# KSS_4_button.net
KiCad netlist of a schematic drawn in Altium Designer
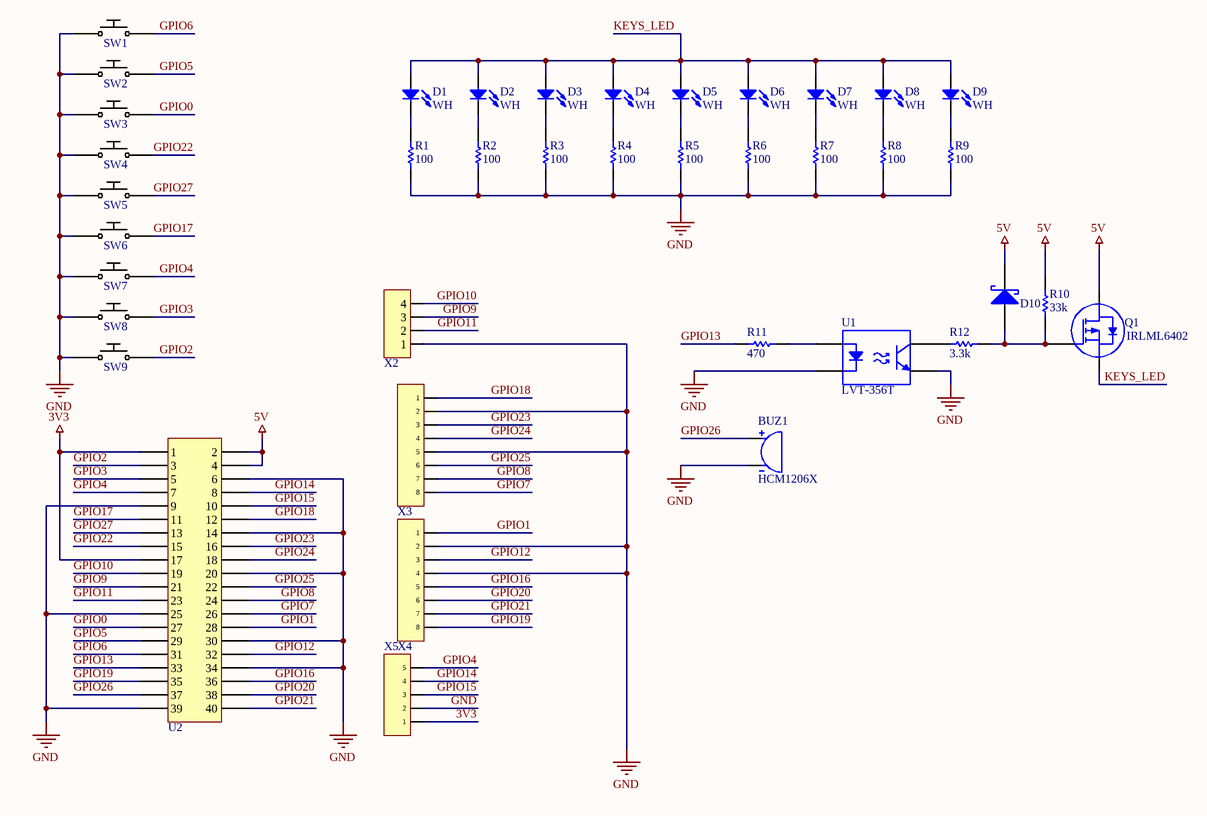
[diagram p0: KSS_4_button.SchDoc]

(export (version "E")
  (design (tool "Eeschema 10.0.6"))
  (components
    (comp (ref "BUZ1")
      (value "HCM1206X")
      (footprint "HCM1206X")
      (description "Buzzer")
      (libsource (lib "COMPONENTS_2022") (part "HCM1206X"))
    )
    (comp (ref "D1")
      (value "WH")
      (footprint "LED_1206/3mm")
      (libsource (lib "COMPONENTS_2022") (part "Diode LED"))
    )
    (comp (ref "D2")
      (value "WH")
      (footprint "LED_1206/3mm")
      (libsource (lib "COMPONENTS_2022") (part "Diode LED"))
    )
    (comp (ref "D3")
      (value "WH")
      (footprint "LED_1206/3mm")
      (libsource (lib "COMPONENTS_2022") (part "Diode LED"))
    )
    (comp (ref "D4")
      (value "WH")
      (footprint "LED_1206/3mm")
      (libsource (lib "COMPONENTS_2022") (part "Diode LED"))
    )
    (comp (ref "D5")
      (value "WH")
      (footprint "LED_1206/3mm")
      (libsource (lib "COMPONENTS_2022") (part "Diode LED"))
    )
    (comp (ref "D6")
      (value "WH")
      (footprint "LED_1206/3mm")
      (libsource (lib "COMPONENTS_2022") (part "Diode LED"))
    )
    (comp (ref "D7")
      (value "WH")
      (footprint "LED_1206/3mm")
      (libsource (lib "COMPONENTS_2022") (part "Diode LED"))
    )
    (comp (ref "D8")
      (value "WH")
      (footprint "LED_1206/3mm")
      (libsource (lib "COMPONENTS_2022") (part "Diode LED"))
    )
    (comp (ref "D9")
      (value "WH")
      (footprint "LED_1206/3mm")
      (libsource (lib "COMPONENTS_2022") (part "Diode LED"))
    )
    (comp (ref "D10")
      (value "SS14")
      (footprint "SMA/DO-214AC")
      (description "Schottky")
      (libsource (lib "COMPONENTS_2022") (part "SS14"))
    )
    (comp (ref "Q1")
      (value "IRLML6402")
      (footprint "SOT23_3_PIN")
      (description "P-MOSFET")
      (libsource (lib "COMPONENTS_2022") (part "IRLML6402"))
    )
    (comp (ref "R1")
      (value "Resistor")
      (fields (field (name "RESISTANCE") "100"))
      (libsource (lib "COMPONENTS_2022") (part "Resistor"))
    )
    (comp (ref "R2")
      (value "Resistor")
      (fields (field (name "RESISTANCE") "100"))
      (libsource (lib "COMPONENTS_2022") (part "Resistor"))
    )
    (comp (ref "R3")
      (value "Resistor")
      (fields (field (name "RESISTANCE") "100"))
      (libsource (lib "COMPONENTS_2022") (part "Resistor"))
    )
    (comp (ref "R4")
      (value "Resistor")
      (fields (field (name "RESISTANCE") "100"))
      (libsource (lib "COMPONENTS_2022") (part "Resistor"))
    )
    (comp (ref "R5")
      (value "Resistor")
      (fields (field (name "RESISTANCE") "100"))
      (libsource (lib "COMPONENTS_2022") (part "Resistor"))
    )
    (comp (ref "R6")
      (value "Resistor")
      (fields (field (name "RESISTANCE") "100"))
      (libsource (lib "COMPONENTS_2022") (part "Resistor"))
    )
    (comp (ref "R7")
      (value "Resistor")
      (fields (field (name "RESISTANCE") "100"))
      (libsource (lib "COMPONENTS_2022") (part "Resistor"))
    )
    (comp (ref "R8")
      (value "Resistor")
      (fields (field (name "RESISTANCE") "100"))
      (libsource (lib "COMPONENTS_2022") (part "Resistor"))
    )
    (comp (ref "R9")
      (value "Resistor")
      (fields (field (name "RESISTANCE") "100"))
      (libsource (lib "COMPONENTS_2022") (part "Resistor"))
    )
    (comp (ref "R10")
      (value "Resistor")
      (footprint "RES_0603")
      (fields (field (name "RESISTANCE") "33k"))
      (libsource (lib "COMPONENTS_2022") (part "Resistor"))
    )
    (comp (ref "R11")
      (value "Resistor")
      (footprint "RES_0603")
      (fields (field (name "RESISTANCE") "470"))
      (libsource (lib "COMPONENTS_2022") (part "Resistor"))
    )
    (comp (ref "R12")
      (value "Resistor")
      (footprint "RES_0603")
      (fields (field (name "RESISTANCE") "3.3k"))
      (libsource (lib "COMPONENTS_2022") (part "Resistor"))
    )
    (comp (ref "SW1")
      (value "Pushbutton")
      (footprint "Key switch Outemu")
      (libsource (lib "COMPONENTS_2022") (part "Pushbutton"))
    )
    (comp (ref "SW2")
      (value "Pushbutton")
      (footprint "Key switch Outemu")
      (libsource (lib "COMPONENTS_2022") (part "Pushbutton"))
    )
    (comp (ref "SW3")
      (value "Pushbutton")
      (footprint "Key switch Outemu")
      (libsource (lib "COMPONENTS_2022") (part "Pushbutton"))
    )
    (comp (ref "SW4")
      (value "Pushbutton")
      (footprint "Key switch Outemu")
      (libsource (lib "COMPONENTS_2022") (part "Pushbutton"))
    )
    (comp (ref "SW5")
      (value "Pushbutton")
      (footprint "Key switch Outemu")
      (libsource (lib "COMPONENTS_2022") (part "Pushbutton"))
    )
    (comp (ref "SW6")
      (value "Pushbutton")
      (footprint "Key switch Outemu")
      (libsource (lib "COMPONENTS_2022") (part "Pushbutton"))
    )
    (comp (ref "SW7")
      (value "Pushbutton")
      (footprint "Key switch Outemu")
      (libsource (lib "COMPONENTS_2022") (part "Pushbutton"))
    )
    (comp (ref "SW8")
      (value "Pushbutton")
      (footprint "Key switch Outemu")
      (libsource (lib "COMPONENTS_2022") (part "Pushbutton"))
    )
    (comp (ref "SW9")
      (value "Pushbutton")
      (footprint "Key switch Outemu")
      (libsource (lib "COMPONENTS_2022") (part "Pushbutton"))
    )
    (comp (ref "U1")
      (value "LVT-356T")
      (footprint "SOP-4")
      (description "Optocoupler")
      (libsource (lib "COMPONENTS_2022") (part "LVT-356T"))
    )
    (comp (ref "U2")
      (value "RASPBERRY_PI_ZERO_W2")
      (footprint "RASPBERRY_PI_ZERO_W2")
      (libsource (lib "COMPONENTS_2022") (part "RASPBERRY_PI_ZERO_W2"))
    )
    (comp (ref "X2")
      (value "Connector_x4")
      (footprint "GROVE_4_pin_2mm_socket")
      (libsource (lib "COMPONENTS_2022") (part "Connector_x4"))
    )
    (comp (ref "X3")
      (value "HEADER_X8")
      (footprint "HEADER_1X8_F")
      (libsource (lib "HEADERS") (part "HEADER_X8"))
    )
    (comp (ref "X4")
      (value "HEADER_X8")
      (footprint "HEADER_1X8_F")
      (libsource (lib "HEADERS") (part "HEADER_X8"))
    )
    (comp (ref "X5") (value "GPS") (footprint "HEADER_1X5_F") (libsource (lib "HEADERS") (part "HEADER_X5")))
  )
  (nets
    (net (code "1") (name "/GPIO0") (class "Default")
      (node (ref "SW3") (pin "2") (pinfunction "2_2") (pintype "passive"))
      (node (ref "U2") (pin "27") (pinfunction "27_27") (pintype "passive"))
    )
    (net (code "2") (name "/GPIO1") (class "Default")
      (node (ref "U2") (pin "28") (pinfunction "28_28") (pintype "passive"))
      (node (ref "X4") (pin "1") (pinfunction "1_1") (pintype "passive"))
    )
    (net (code "3") (name "/GPIO2") (class "Default")
      (node (ref "SW9") (pin "2") (pinfunction "2_2") (pintype "passive"))
      (node (ref "U2") (pin "3") (pinfunction "3_3") (pintype "passive"))
    )
    (net (code "4") (name "/GPIO3") (class "Default")
      (node (ref "SW8") (pin "2") (pinfunction "2_2") (pintype "passive"))
      (node (ref "U2") (pin "5") (pinfunction "5_5") (pintype "passive"))
    )
    (net (code "5") (name "/GPIO4") (class "Default")
      (node (ref "SW7") (pin "2") (pinfunction "2_2") (pintype "passive"))
      (node (ref "U2") (pin "7") (pinfunction "7_7") (pintype "passive"))
      (node (ref "X5") (pin "5") (pinfunction "5_5") (pintype "passive"))
    )
    (net (code "6") (name "/GPIO5") (class "Default")
      (node (ref "SW2") (pin "2") (pinfunction "2_2") (pintype "passive"))
      (node (ref "U2") (pin "29") (pinfunction "29_29") (pintype "passive"))
    )
    (net (code "7") (name "/GPIO6") (class "Default")
      (node (ref "SW1") (pin "2") (pinfunction "2_2") (pintype "passive"))
      (node (ref "U2") (pin "31") (pinfunction "31_31") (pintype "passive"))
    )
    (net (code "8") (name "/GPIO7") (class "Default")
      (node (ref "U2") (pin "26") (pinfunction "26_26") (pintype "passive"))
      (node (ref "X3") (pin "8") (pinfunction "8_8") (pintype "passive"))
    )
    (net (code "9") (name "/GPIO8") (class "Default")
      (node (ref "U2") (pin "24") (pinfunction "24_24") (pintype "passive"))
      (node (ref "X3") (pin "7") (pinfunction "7_7") (pintype "passive"))
    )
    (net (code "10") (name "/GPIO9") (class "Default")
      (node (ref "U2") (pin "21") (pinfunction "21_21") (pintype "passive"))
      (node (ref "X2") (pin "3") (pinfunction "3_3") (pintype "passive"))
    )
    (net (code "11") (name "/GPIO10") (class "Default")
      (node (ref "U2") (pin "19") (pinfunction "19_19") (pintype "passive"))
      (node (ref "X2") (pin "4") (pinfunction "4_4") (pintype "passive"))
    )
    (net (code "12") (name "/GPIO11") (class "Default")
      (node (ref "U2") (pin "23") (pinfunction "23_23") (pintype "passive"))
      (node (ref "X2") (pin "2") (pinfunction "2_2") (pintype "passive"))
    )
    (net (code "13") (name "/GPIO12") (class "Default")
      (node (ref "U2") (pin "32") (pinfunction "32_32") (pintype "passive"))
      (node (ref "X4") (pin "3") (pinfunction "3_3") (pintype "passive"))
    )
    (net (code "14") (name "/GPIO13") (class "Default")
      (node (ref "R11") (pin "1") (pinfunction "1_1") (pintype "passive"))
      (node (ref "U2") (pin "33") (pinfunction "33_33") (pintype "passive"))
    )
    (net (code "15") (name "/GPIO14") (class "Default")
      (node (ref "U2") (pin "8") (pinfunction "8_8") (pintype "passive"))
      (node (ref "X5") (pin "4") (pinfunction "4_4") (pintype "passive"))
    )
    (net (code "16") (name "/GPIO15") (class "Default")
      (node (ref "U2") (pin "10") (pinfunction "10_10") (pintype "passive"))
      (node (ref "X5") (pin "3") (pinfunction "3_3") (pintype "passive"))
    )
    (net (code "17") (name "/GPIO16") (class "Default")
      (node (ref "U2") (pin "36") (pinfunction "36_36") (pintype "passive"))
      (node (ref "X4") (pin "5") (pinfunction "5_5") (pintype "passive"))
    )
    (net (code "18") (name "/GPIO17") (class "Default")
      (node (ref "SW6") (pin "2") (pinfunction "2_2") (pintype "passive"))
      (node (ref "U2") (pin "11") (pinfunction "11_11") (pintype "passive"))
    )
    (net (code "19") (name "/GPIO18") (class "Default")
      (node (ref "U2") (pin "12") (pinfunction "12_12") (pintype "passive"))
      (node (ref "X3") (pin "1") (pinfunction "1_1") (pintype "passive"))
    )
    (net (code "20") (name "/GPIO19") (class "Default")
      (node (ref "U2") (pin "35") (pinfunction "35_35") (pintype "passive"))
      (node (ref "X4") (pin "8") (pinfunction "8_8") (pintype "passive"))
    )
    (net (code "21") (name "/GPIO20") (class "Default")
      (node (ref "U2") (pin "38") (pinfunction "38_38") (pintype "passive"))
      (node (ref "X4") (pin "6") (pinfunction "6_6") (pintype "passive"))
    )
    (net (code "22") (name "/GPIO21") (class "Default")
      (node (ref "U2") (pin "40") (pinfunction "40_40") (pintype "passive"))
      (node (ref "X4") (pin "7") (pinfunction "7_7") (pintype "passive"))
    )
    (net (code "23") (name "/GPIO22") (class "Default")
      (node (ref "SW4") (pin "2") (pinfunction "2_2") (pintype "passive"))
      (node (ref "U2") (pin "15") (pinfunction "15_15") (pintype "passive"))
    )
    (net (code "24") (name "/GPIO23") (class "Default")
      (node (ref "U2") (pin "16") (pinfunction "16_16") (pintype "passive"))
      (node (ref "X3") (pin "3") (pinfunction "3_3") (pintype "passive"))
    )
    (net (code "25") (name "/GPIO24") (class "Default")
      (node (ref "U2") (pin "18") (pinfunction "18_18") (pintype "passive"))
      (node (ref "X3") (pin "4") (pinfunction "4_4") (pintype "passive"))
    )
    (net (code "26") (name "/GPIO25") (class "Default")
      (node (ref "U2") (pin "22") (pinfunction "22_22") (pintype "passive"))
      (node (ref "X3") (pin "6") (pinfunction "6_6") (pintype "passive"))
    )
    (net (code "27") (name "/GPIO26") (class "Default")
      (node (ref "BUZ1") (pin "1") (pinfunction "+_1") (pintype "passive"))
      (node (ref "U2") (pin "37") (pinfunction "37_37") (pintype "passive"))
    )
    (net (code "28") (name "/GPIO27") (class "Default")
      (node (ref "SW5") (pin "2") (pinfunction "2_2") (pintype "passive"))
      (node (ref "U2") (pin "13") (pinfunction "13_13") (pintype "passive"))
    )
    (net (code "29") (name "/KEYS_LED") (class "Default")
      (node (ref "D1") (pin "1") (pinfunction "A_1") (pintype "passive"))
      (node (ref "D2") (pin "1") (pinfunction "A_1") (pintype "passive"))
      (node (ref "D3") (pin "1") (pinfunction "A_1") (pintype "passive"))
      (node (ref "D4") (pin "1") (pinfunction "A_1") (pintype "passive"))
      (node (ref "D5") (pin "1") (pinfunction "A_1") (pintype "passive"))
      (node (ref "D6") (pin "1") (pinfunction "A_1") (pintype "passive"))
      (node (ref "D7") (pin "1") (pinfunction "A_1") (pintype "passive"))
      (node (ref "D8") (pin "1") (pinfunction "A_1") (pintype "passive"))
      (node (ref "D9") (pin "1") (pinfunction "A_1") (pintype "passive"))
      (node (ref "Q1") (pin "2") (pinfunction "S_2") (pintype "passive"))
    )
    (net (code "30") (name "3V3") (class "Default")
      (node (ref "U2") (pin "1") (pinfunction "1_1") (pintype "passive"))
      (node (ref "U2") (pin "17") (pinfunction "17_17") (pintype "passive"))
      (node (ref "X5") (pin "1") (pinfunction "1_1") (pintype "passive"))
    )
    (net (code "31") (name "5V") (class "Default")
      (node (ref "D10") (pin "2") (pinfunction "K_2") (pintype "passive"))
      (node (ref "Q1") (pin "3") (pinfunction "D_3") (pintype "passive"))
      (node (ref "R10") (pin "1") (pinfunction "1_1") (pintype "passive"))
      (node (ref "U2") (pin "2") (pinfunction "2_2") (pintype "passive"))
      (node (ref "U2") (pin "4") (pinfunction "4_4") (pintype "passive"))
    )
    (net (code "32") (name "GND") (class "Default")
      (node (ref "BUZ1") (pin "2") (pinfunction "-_2") (pintype "passive"))
      (node (ref "R1") (pin "1") (pinfunction "1_1") (pintype "passive"))
      (node (ref "R2") (pin "1") (pinfunction "1_1") (pintype "passive"))
      (node (ref "R3") (pin "1") (pinfunction "1_1") (pintype "passive"))
      (node (ref "R4") (pin "1") (pinfunction "1_1") (pintype "passive"))
      (node (ref "R5") (pin "1") (pinfunction "1_1") (pintype "passive"))
      (node (ref "R6") (pin "1") (pinfunction "1_1") (pintype "passive"))
      (node (ref "R7") (pin "1") (pinfunction "1_1") (pintype "passive"))
      (node (ref "R8") (pin "1") (pinfunction "1_1") (pintype "passive"))
      (node (ref "R9") (pin "1") (pinfunction "1_1") (pintype "passive"))
      (node (ref "SW1") (pin "1") (pinfunction "1_1") (pintype "passive"))
      (node (ref "SW2") (pin "1") (pinfunction "1_1") (pintype "passive"))
      (node (ref "SW3") (pin "1") (pinfunction "1_1") (pintype "passive"))
      (node (ref "SW4") (pin "1") (pinfunction "1_1") (pintype "passive"))
      (node (ref "SW5") (pin "1") (pinfunction "1_1") (pintype "passive"))
      (node (ref "SW6") (pin "1") (pinfunction "1_1") (pintype "passive"))
      (node (ref "SW7") (pin "1") (pinfunction "1_1") (pintype "passive"))
      (node (ref "SW8") (pin "1") (pinfunction "1_1") (pintype "passive"))
      (node (ref "SW9") (pin "1") (pinfunction "1_1") (pintype "passive"))
      (node (ref "U1") (pin "2") (pinfunction "K_2") (pintype "passive"))
      (node (ref "U1") (pin "3") (pinfunction "E_3") (pintype "passive"))
      (node (ref "U2") (pin "14") (pinfunction "14_14") (pintype "passive"))
      (node (ref "U2") (pin "20") (pinfunction "20_20") (pintype "passive"))
      (node (ref "U2") (pin "25") (pinfunction "25_25") (pintype "passive"))
      (node (ref "U2") (pin "30") (pinfunction "30_30") (pintype "passive"))
      (node (ref "U2") (pin "34") (pinfunction "34_34") (pintype "passive"))
      (node (ref "U2") (pin "39") (pinfunction "39_39") (pintype "passive"))
      (node (ref "U2") (pin "6") (pinfunction "6_6") (pintype "passive"))
      (node (ref "U2") (pin "9") (pinfunction "9_9") (pintype "passive"))
      (node (ref "X2") (pin "1") (pinfunction "1_1") (pintype "passive"))
      (node (ref "X3") (pin "2") (pinfunction "2_2") (pintype "passive"))
      (node (ref "X3") (pin "5") (pinfunction "5_5") (pintype "passive"))
      (node (ref "X4") (pin "2") (pinfunction "2_2") (pintype "passive"))
      (node (ref "X4") (pin "4") (pinfunction "4_4") (pintype "passive"))
      (node (ref "X5") (pin "2") (pinfunction "2_2") (pintype "passive"))
    )
    (net (code "33") (name "Net-(D1-K)") (class "Default")
      (node (ref "D1") (pin "2") (pinfunction "K_2") (pintype "passive"))
      (node (ref "R1") (pin "2") (pinfunction "2_2") (pintype "passive"))
    )
    (net (code "34") (name "Net-(D2-K)") (class "Default")
      (node (ref "D2") (pin "2") (pinfunction "K_2") (pintype "passive"))
      (node (ref "R2") (pin "2") (pinfunction "2_2") (pintype "passive"))
    )
    (net (code "35") (name "Net-(D3-K)") (class "Default")
      (node (ref "D3") (pin "2") (pinfunction "K_2") (pintype "passive"))
      (node (ref "R3") (pin "2") (pinfunction "2_2") (pintype "passive"))
    )
    (net (code "36") (name "Net-(D4-K)") (class "Default")
      (node (ref "D4") (pin "2") (pinfunction "K_2") (pintype "passive"))
      (node (ref "R4") (pin "2") (pinfunction "2_2") (pintype "passive"))
    )
    (net (code "37") (name "Net-(D5-K)") (class "Default")
      (node (ref "D5") (pin "2") (pinfunction "K_2") (pintype "passive"))
      (node (ref "R5") (pin "2") (pinfunction "2_2") (pintype "passive"))
    )
    (net (code "38") (name "Net-(D6-K)") (class "Default")
      (node (ref "D6") (pin "2") (pinfunction "K_2") (pintype "passive"))
      (node (ref "R6") (pin "2") (pinfunction "2_2") (pintype "passive"))
    )
    (net (code "39") (name "Net-(D7-K)") (class "Default")
      (node (ref "D7") (pin "2") (pinfunction "K_2") (pintype "passive"))
      (node (ref "R7") (pin "2") (pinfunction "2_2") (pintype "passive"))
    )
    (net (code "40") (name "Net-(D8-K)") (class "Default")
      (node (ref "D8") (pin "2") (pinfunction "K_2") (pintype "passive"))
      (node (ref "R8") (pin "2") (pinfunction "2_2") (pintype "passive"))
    )
    (net (code "41") (name "Net-(D9-K)") (class "Default")
      (node (ref "D9") (pin "2") (pinfunction "K_2") (pintype "passive"))
      (node (ref "R9") (pin "2") (pinfunction "2_2") (pintype "passive"))
    )
    (net (code "42") (name "Net-(D10-A)") (class "Default")
      (node (ref "D10") (pin "1") (pinfunction "A_1") (pintype "passive"))
      (node (ref "Q1") (pin "1") (pinfunction "G_1") (pintype "passive"))
      (node (ref "R10") (pin "2") (pinfunction "2_2") (pintype "passive"))
      (node (ref "R12") (pin "2") (pinfunction "2_2") (pintype "passive"))
    )
    (net (code "43") (name "Net-(U1-A)") (class "Default")
      (node (ref "R11") (pin "2") (pinfunction "2_2") (pintype "passive"))
      (node (ref "U1") (pin "1") (pinfunction "A_1") (pintype "passive"))
    )
    (net (code "44") (name "Net-(U1-C)") (class "Default")
      (node (ref "R12") (pin "1") (pinfunction "1_1") (pintype "passive"))
      (node (ref "U1") (pin "4") (pinfunction "C_4") (pintype "passive"))
    )
  )
)
